# Communication.net
KiCad netlist of a schematic drawn in Altium Designer
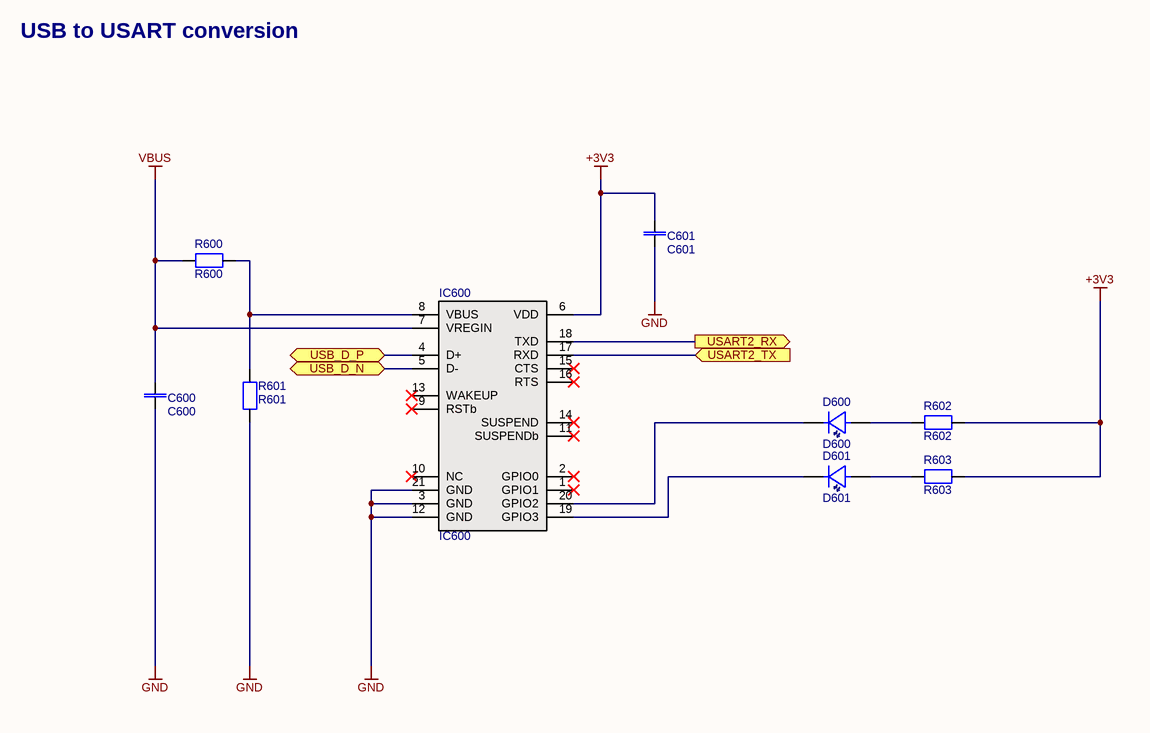
[diagram p0: Communication.SchDoc]

(export (version "E")
  (design (tool "Eeschema 10.0.6"))
  (components
    (comp (ref "C600")
      (value "C 1uF 50V")
      (footprint "0805-2012")
      (description "Capacitor")
      (fields
        (field (name "MANUFACTURER") "Murata Electronics North America")
        (field (name "MANUFACTURER PART NUMBER") "GRM21BF51H105ZA12L")
      )
      (libsource (lib "Database_Libs1") (part "Kondensator"))
    )
    (comp (ref "C601")
      (value "C 1uF 50V")
      (footprint "0805-2012")
      (description "Capacitor")
      (fields
        (field (name "MANUFACTURER") "Murata Electronics North America")
        (field (name "MANUFACTURER PART NUMBER") "GRM21BF51H105ZA12L")
      )
      (libsource (lib "Database_Libs1") (part "Kondensator"))
    )
    (comp (ref "D600")
      (value "LED SMD 0805")
      (footprint "0805_LED")
      (description "LED")
      (fields
        (field (name "MANUFACTURER") "Dialight")
        (field (name "MANUFACTURER PART NUMBER") "5988170107F")
        (field (name "VERIFICATION") "25.01.2013 MLP")
      )
      (libsource (lib "Database_Libs1") (part "LED"))
    )
    (comp (ref "D601")
      (value "LED SMD 0805")
      (footprint "0805_LED")
      (description "LED")
      (fields
        (field (name "MANUFACTURER") "Dialight")
        (field (name "MANUFACTURER PART NUMBER") "5988170107F")
        (field (name "VERIFICATION") "25.01.2013 MLP")
      )
      (libsource (lib "Database_Libs1") (part "LED"))
    )
    (comp (ref "IC600")
      (value "CP2102N-A02")
      (footprint "GQFN20R")
      (description "Interface")
      (fields
        (field (name "MANUFACTURER") "Silicon Labs")
        (field (name "MANUFACTURER PART NUMBER") "CP2102N-A02-GQFN20")
      )
      (libsource (lib "Database_Libs1") (part "CP2102N-A02"))
    )
    (comp (ref "R600")
      (value "R 22k 1%")
      (footprint "0603-1608")
      (description "Resistor")
      (fields
        (field (name "MANUFACTURER") "Vishay Dale")
        (field (name "MANUFACTURER PART NUMBER") "CRCW060322K0FKEA")
        (field (name "VERIFICATION") "05.07.2012 OPT")
      )
      (libsource (lib "Database_Libs1") (part "Resistor"))
    )
    (comp (ref "R601")
      (value "R 47K 1%")
      (footprint "0603-1608")
      (description "Resistor")
      (fields
        (field (name "MANUFACTURER") "Vishay Dale")
        (field (name "MANUFACTURER PART NUMBER") "CRCW060347K0FKEA")
        (field (name "VERIFICATION") "05.07.2012 OPT")
      )
      (libsource (lib "Database_Libs1") (part "Resistor"))
    )
    (comp (ref "R602")
      (value "R 560E 1%")
      (footprint "0805-2012")
      (description "Resistor")
      (fields
        (field (name "MANUFACTURER") "Panasonic Electronic Components")
        (field (name "MANUFACTURER PART NUMBER") "ERJ-6ENF5600V")
      )
      (libsource (lib "Database_Libs1") (part "Resistor"))
    )
    (comp (ref "R603")
      (value "R 560E 1%")
      (footprint "0805-2012")
      (description "Resistor")
      (fields
        (field (name "MANUFACTURER") "Panasonic Electronic Components")
        (field (name "MANUFACTURER PART NUMBER") "ERJ-6ENF5600V")
      )
      (libsource (lib "Database_Libs1") (part "Resistor"))
    )
  )
  (nets
    (net (code "1") (name "+3V3") (class "Default")
      (node (ref "C601") (pin "1") (pinfunction "1_1") (pintype "passive"))
      (node (ref "IC600") (pin "6") (pinfunction "VDD_6") (pintype "passive"))
      (node (ref "R602") (pin "2") (pinfunction "2_2") (pintype "passive"))
      (node (ref "R603") (pin "2") (pinfunction "2_2") (pintype "passive"))
    )
    (net (code "2") (name "/USART2_RX") (class "Default")
      (node (ref "IC600") (pin "18") (pinfunction "TXD_18") (pintype "passive"))
    )
    (net (code "3") (name "/USART2_TX") (class "Default")
      (node (ref "IC600") (pin "17") (pinfunction "RXD_17") (pintype "passive"))
    )
    (net (code "4") (name "/USB_D_N") (class "Default")
      (node (ref "IC600") (pin "5") (pinfunction "D-_5") (pintype "passive"))
    )
    (net (code "5") (name "/USB_D_P") (class "Default")
      (node (ref "IC600") (pin "4") (pinfunction "D+_4") (pintype "passive"))
    )
    (net (code "6") (name "GND") (class "Default")
      (node (ref "C600") (pin "2") (pinfunction "2_2") (pintype "passive"))
      (node (ref "C601") (pin "2") (pinfunction "2_2") (pintype "passive"))
      (node (ref "IC600") (pin "12") (pinfunction "GND_12") (pintype "passive"))
      (node (ref "IC600") (pin "21") (pinfunction "GND_21") (pintype "passive"))
      (node (ref "IC600") (pin "3") (pinfunction "GND_3") (pintype "passive"))
      (node (ref "R601") (pin "2") (pinfunction "2_2") (pintype "passive"))
    )
    (net (code "7") (name "Net-(D600-A)") (class "Default")
      (node (ref "D600") (pin "1") (pinfunction "A_1") (pintype "passive"))
      (node (ref "R602") (pin "1") (pinfunction "1_1") (pintype "passive"))
    )
    (net (code "8") (name "Net-(D600-K)") (class "Default")
      (node (ref "D600") (pin "2") (pinfunction "K_2") (pintype "passive"))
      (node (ref "IC600") (pin "20") (pinfunction "GPIO2_20") (pintype "passive"))
    )
    (net (code "9") (name "Net-(D601-A)") (class "Default")
      (node (ref "D601") (pin "1") (pinfunction "A_1") (pintype "passive"))
      (node (ref "R603") (pin "1") (pinfunction "1_1") (pintype "passive"))
    )
    (net (code "10") (name "Net-(D601-K)") (class "Default")
      (node (ref "D601") (pin "2") (pinfunction "K_2") (pintype "passive"))
      (node (ref "IC600") (pin "19") (pinfunction "GPIO3_19") (pintype "passive"))
    )
    (net (code "11") (name "Net-(IC600-VBUS)") (class "Default")
      (node (ref "IC600") (pin "8") (pinfunction "VBUS_8") (pintype "passive"))
      (node (ref "R600") (pin "2") (pinfunction "2_2") (pintype "passive"))
      (node (ref "R601") (pin "1") (pinfunction "1_1") (pintype "passive"))
    )
    (net (code "12") (name "VBUS") (class "Default")
      (node (ref "C600") (pin "1") (pinfunction "1_1") (pintype "passive"))
      (node (ref "IC600") (pin "7") (pinfunction "VREGIN_7") (pintype "passive"))
      (node (ref "R600") (pin "1") (pinfunction "1_1") (pintype "passive"))
    )
    (net (code "13") (name "unconnected-(IC600-CTS-Pad15)") (class "Default")
      (node (ref "IC600") (pin "15") (pinfunction "CTS_15") (pintype "passive+no_connect"))
    )
    (net (code "14") (name "unconnected-(IC600-GPIO0-Pad2)") (class "Default")
      (node (ref "IC600") (pin "2") (pinfunction "GPIO0_2") (pintype "passive+no_connect"))
    )
    (net (code "15") (name "unconnected-(IC600-GPIO1-Pad1)") (class "Default")
      (node (ref "IC600") (pin "1") (pinfunction "GPIO1_1") (pintype "passive+no_connect"))
    )
    (net (code "16") (name "unconnected-(IC600-NC-Pad10)") (class "Default")
      (node (ref "IC600") (pin "10") (pinfunction "NC_10") (pintype "passive+no_connect"))
    )
    (net (code "17") (name "unconnected-(IC600-RSTb-Pad9)") (class "Default")
      (node (ref "IC600") (pin "9") (pinfunction "RSTb_9") (pintype "passive+no_connect"))
    )
    (net (code "18") (name "unconnected-(IC600-RTS-Pad16)") (class "Default")
      (node (ref "IC600") (pin "16") (pinfunction "RTS_16") (pintype "passive+no_connect"))
    )
    (net (code "19") (name "unconnected-(IC600-SUSPEND-Pad14)") (class "Default")
      (node (ref "IC600") (pin "14") (pinfunction "SUSPEND_14") (pintype "passive+no_connect"))
    )
    (net (code "20") (name "unconnected-(IC600-SUSPENDb-Pad11)") (class "Default")
      (node (ref "IC600") (pin "11") (pinfunction "SUSPENDb_11") (pintype "passive+no_connect"))
    )
    (net (code "21") (name "unconnected-(IC600-WAKEUP-Pad13)") (class "Default")
      (node (ref "IC600") (pin "13") (pinfunction "WAKEUP_13") (pintype "passive+no_connect"))
    )
  )
)
